# 12_-MCU_INPUTS.net
KiCad netlist of a schematic drawn in Altium Designer
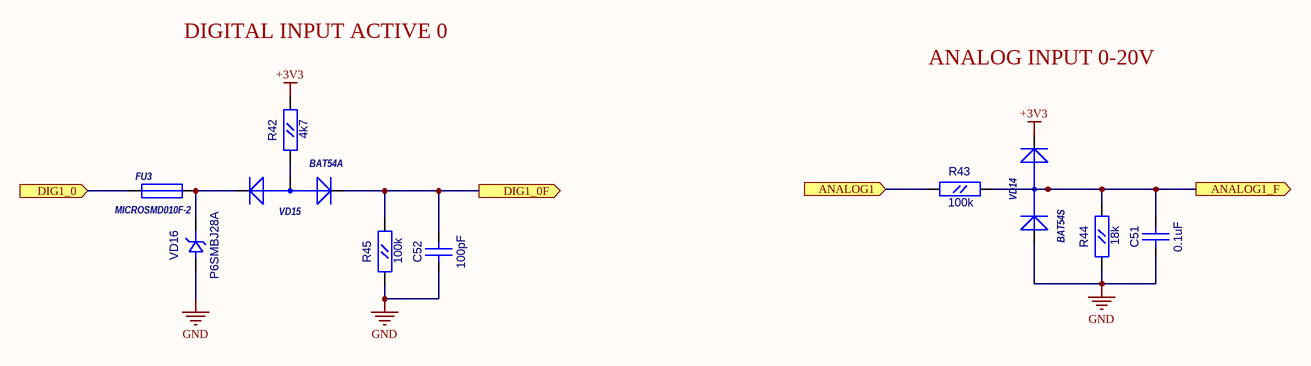
[diagram p0: [12]-MCU_INPUTS.SchDoc]

(export (version "E")
  (design (tool "Eeschema 10.0.6"))
  (components
    (comp (ref "C51")
      (value "0.1uF")
      (footprint "CC0603")
      (description "CC0603")
      (libsource (lib "gprs_modem_2") (part "CC0603"))
    )
    (comp (ref "C52")
      (value "100pF")
      (footprint "CC0603")
      (description "CC0603")
      (libsource (lib "gprs_modem_2") (part "CC0603"))
    )
    (comp (ref "FU3")
      (value "MICROSMD010F-2")
      (footprint "RC1210")
      (description "MICROSMD")
      (libsource (lib "gprs_modem_2") (part "MICROSMD"))
    )
    (comp (ref "R42")
      (value "4k7")
      (footprint "RC0603")
      (description "RC0603")
      (libsource (lib "gprs_modem_2") (part "RC0603"))
    )
    (comp (ref "R43")
      (value "100k")
      (footprint "RC0603")
      (description "RC0603")
      (libsource (lib "gprs_modem_2") (part "RC0603"))
    )
    (comp (ref "R44")
      (value "18k")
      (footprint "RC0603")
      (description "RC0603")
      (libsource (lib "gprs_modem_2") (part "RC0603"))
    )
    (comp (ref "R45")
      (value "100k")
      (footprint "RC0603")
      (description "RC0603")
      (libsource (lib "gprs_modem_2") (part "RC0603"))
    )
    (comp (ref "VD14")
      (value "BAT54S")
      (footprint "SOT-23(GSD)")
      (description "1.0 Ampere General Purpose Rectifier")
      (libsource (lib "gprs_modem_2") (part "BAT54S"))
    )
    (comp (ref "VD15")
      (value "BAT54A")
      (footprint "SOT-23(123)")
      (description "1.0 Ampere General Purpose Rectifier")
      (libsource (lib "gprs_modem_2") (part "BAT54A"))
    )
    (comp (ref "VD16")
      (value "P6SMBJ28A")
      (footprint "SMB")
      (description "SMBJ")
      (libsource (lib "gprs_modem_2") (part "SMBJ"))
    )
  )
  (nets
    (net (code "1") (name "+3V3") (class "Default")
      (node (ref "R42") (pin "2") (pinfunction "B_2") (pintype "passive"))
      (node (ref "VD14") (pin "2") (pinfunction "K_2") (pintype "passive"))
    )
    (net (code "2") (name "/ANALOG1") (class "Default")
      (node (ref "R43") (pin "1") (pinfunction "A_1") (pintype "passive"))
    )
    (net (code "3") (name "/ANALOG1_F") (class "Default")
      (node (ref "C51") (pin "2") (pinfunction "B_2") (pintype "passive"))
      (node (ref "R43") (pin "2") (pinfunction "B_2") (pintype "passive"))
      (node (ref "R44") (pin "2") (pinfunction "B_2") (pintype "passive"))
      (node (ref "VD14") (pin "3") (pinfunction "AK_3") (pintype "passive"))
    )
    (net (code "4") (name "/DIG1_0") (class "Default") (node (ref "FU3") (pin "1") (pintype "passive")))
    (net (code "5") (name "/DIG1_0F") (class "Default")
      (node (ref "C52") (pin "2") (pinfunction "B_2") (pintype "passive"))
      (node (ref "R45") (pin "2") (pinfunction "B_2") (pintype "passive"))
      (node (ref "VD15") (pin "1") (pinfunction "K_1") (pintype "passive"))
    )
    (net (code "6") (name "GND") (class "Default")
      (node (ref "C51") (pin "1") (pinfunction "A_1") (pintype "passive"))
      (node (ref "C52") (pin "1") (pinfunction "A_1") (pintype "passive"))
      (node (ref "R44") (pin "1") (pinfunction "A_1") (pintype "passive"))
      (node (ref "R45") (pin "1") (pinfunction "A_1") (pintype "passive"))
      (node (ref "VD14") (pin "1") (pinfunction "A_1") (pintype "passive"))
      (node (ref "VD16") (pin "1") (pinfunction "A_1") (pintype "passive"))
    )
    (net (code "7") (name "Net-(R42-A)") (class "Default")
      (node (ref "R42") (pin "1") (pinfunction "A_1") (pintype "passive"))
      (node (ref "VD15") (pin "3") (pinfunction "A_3") (pintype "passive"))
    )
    (net (code "8") (name "Net-(VD16-K)") (class "Default")
      (node (ref "FU3") (pin "2") (pintype "passive"))
      (node (ref "VD15") (pin "2") (pinfunction "K_2") (pintype "passive"))
      (node (ref "VD16") (pin "2") (pinfunction "K_2") (pintype "passive"))
    )
  )
)
